# System_wired.net
KiCad netlist of a schematic drawn in Altium Designer
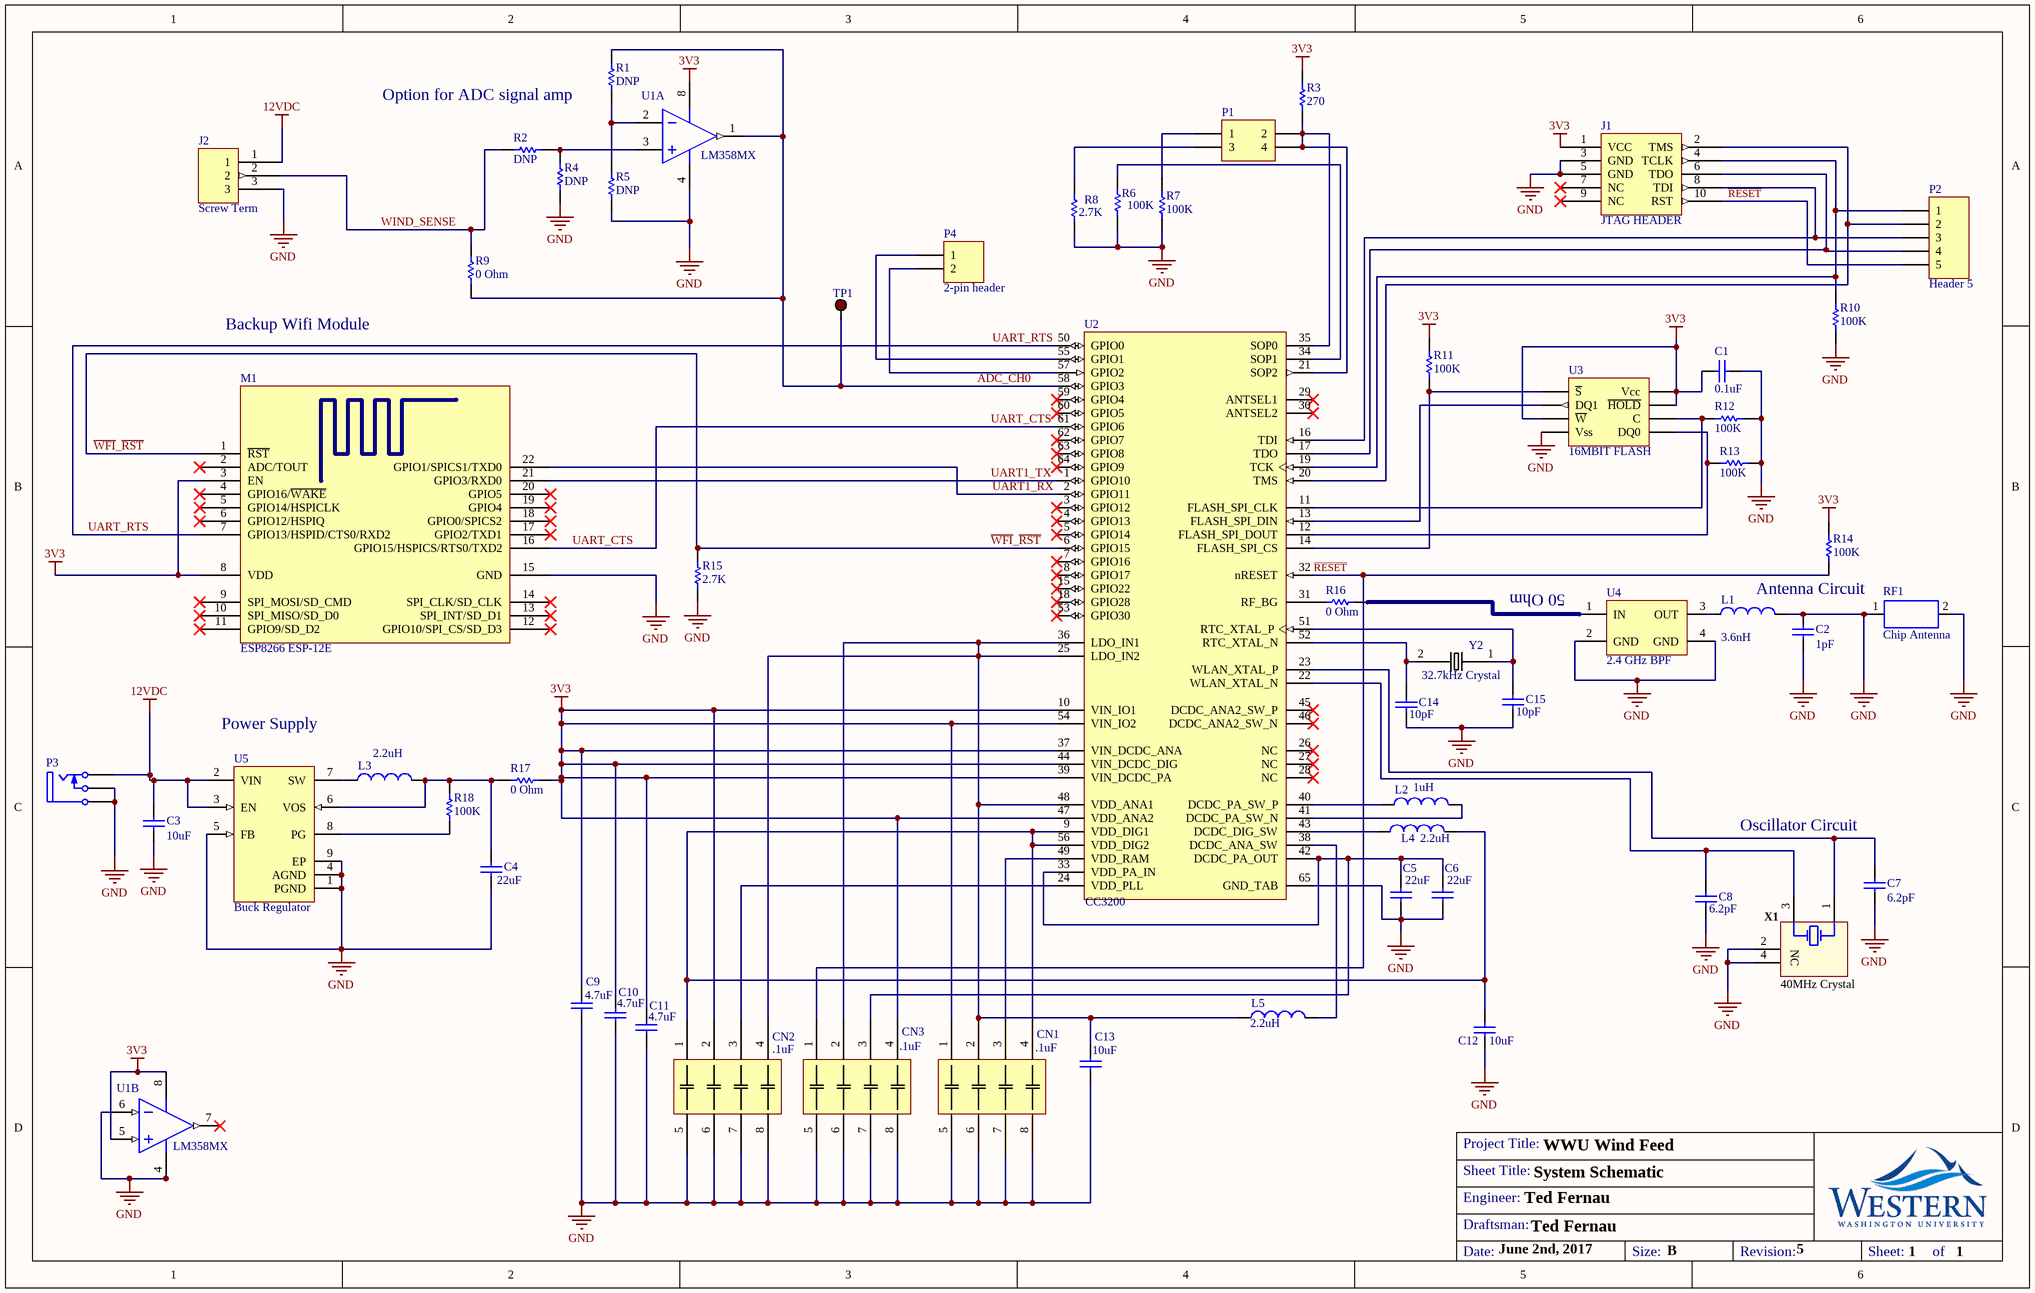
[diagram p0: System_wired.SchDoc]

(export (version "E")
  (design (tool "Eeschema 10.0.6"))
  (components
    (comp (ref "C1")
      (value "0.1uF")
      (footprint "CAPC0603(1608)100_M")
      (description "CAP 10uF 10V ±20% 0603 (1608 Metric) Thickness 1mm SMD")
      (fields (field (name "TOLERANCE") "Â±20%") (field (name "Comment") "CAP 10uF 10V 0603(1608)"))
      (libsource (lib "Altium Content Vault") (part "CMP-1035-02800-1"))
    )
    (comp (ref "C2")
      (value "1pF")
      (footprint "CAPC0603(1608)100_M")
      (description "CAP 10uF 10V ±20% 0603 (1608 Metric) Thickness 1mm SMD")
      (fields (field (name "TOLERANCE") "Â±20%") (field (name "Comment") "CAP 10uF 10V 0603(1608)"))
      (libsource (lib "Altium Content Vault") (part "CMP-1035-02800-1"))
    )
    (comp (ref "C3")
      (value "10uF")
      (footprint "CAPC0603(1608)100_M")
      (description "CAP 10uF 10V ±20% 0603 (1608 Metric) Thickness 1mm SMD")
      (fields (field (name "TOLERANCE") "Â±20%") (field (name "Comment") "CAP 10uF 10V 0603(1608)"))
      (libsource (lib "Altium Content Vault") (part "CMP-1035-02800-1"))
    )
    (comp (ref "C4")
      (value "22uF")
      (footprint "CAPC0603(1608)100_L")
      (description "0603 (1608 Metric) Chip Capacitor")
      (libsource (lib "Altium Content Vault") (part "CMP-1590-00005-1"))
    )
    (comp (ref "C5")
      (value "22uF")
      (footprint "CAPC0603(1608)100_M")
      (description "CAP 10uF 10V ±20% 0603 (1608 Metric) Thickness 1mm SMD")
      (fields (field (name "TOLERANCE") "Â±20%") (field (name "Comment") "CAP 10uF 10V 0603(1608)"))
      (libsource (lib "Altium Content Vault") (part "CMP-1035-02800-1"))
    )
    (comp (ref "C6")
      (value "22uF")
      (footprint "CAPC0603(1608)100_M")
      (description "CAP 10uF 10V ±20% 0603 (1608 Metric) Thickness 1mm SMD")
      (fields (field (name "TOLERANCE") "Â±20%") (field (name "Comment") "CAP 10uF 10V 0603(1608)"))
      (libsource (lib "Altium Content Vault") (part "CMP-1035-02800-1"))
    )
    (comp (ref "C7")
      (value "6.2pF")
      (footprint "CAPC0603(1608)100_M")
      (description "CAP 10uF 10V ±20% 0603 (1608 Metric) Thickness 1mm SMD")
      (fields (field (name "TOLERANCE") "Â±20%") (field (name "Comment") "CAP 10uF 10V 0603(1608)"))
      (libsource (lib "Altium Content Vault") (part "CMP-1035-02800-1"))
    )
    (comp (ref "C8")
      (value "6.2pF")
      (footprint "CAPC0603(1608)100_M")
      (description "CAP 10uF 10V ±20% 0603 (1608 Metric) Thickness 1mm SMD")
      (fields (field (name "TOLERANCE") "Â±20%") (field (name "Comment") "CAP 10uF 10V 0603(1608)"))
      (libsource (lib "Altium Content Vault") (part "CMP-1035-02800-1"))
    )
    (comp (ref "C9")
      (value "4.7uF")
      (footprint "CAPC0603(1608)100_M")
      (description "CAP 10uF 10V ±20% 0603 (1608 Metric) Thickness 1mm SMD")
      (fields (field (name "TOLERANCE") "Â±20%") (field (name "Comment") "CAP 10uF 10V 0603(1608)"))
      (libsource (lib "Altium Content Vault") (part "CMP-1035-02800-1"))
    )
    (comp (ref "C10")
      (value "4.7uF")
      (footprint "CAPC0603(1608)100_M")
      (description "CAP 10uF 10V ±20% 0603 (1608 Metric) Thickness 1mm SMD")
      (fields (field (name "TOLERANCE") "Â±20%") (field (name "Comment") "CAP 10uF 10V 0603(1608)"))
      (libsource (lib "Altium Content Vault") (part "CMP-1035-02800-1"))
    )
    (comp (ref "C11")
      (value "4.7uF")
      (footprint "CAPC0603(1608)100_M")
      (description "CAP 10uF 10V ±20% 0603 (1608 Metric) Thickness 1mm SMD")
      (fields (field (name "TOLERANCE") "Â±20%") (field (name "Comment") "CAP 10uF 10V 0603(1608)"))
      (libsource (lib "Altium Content Vault") (part "CMP-1035-02800-1"))
    )
    (comp (ref "C12")
      (value "10uF")
      (footprint "CAPC0603(1608)100_M")
      (description "CAP 10uF 10V ±20% 0603 (1608 Metric) Thickness 1mm SMD")
      (fields (field (name "TOLERANCE") "Â±20%") (field (name "Comment") "CAP 10uF 10V 0603(1608)"))
      (libsource (lib "Altium Content Vault") (part "CMP-1035-02800-1"))
    )
    (comp (ref "C13")
      (value "10uF")
      (footprint "CAPC0603(1608)100_M")
      (description "CAP 10uF 10V ±20% 0603 (1608 Metric) Thickness 1mm SMD")
      (fields (field (name "TOLERANCE") "Â±20%") (field (name "Comment") "CAP 10uF 10V 0603(1608)"))
      (libsource (lib "Altium Content Vault") (part "CMP-1035-02800-1"))
    )
    (comp (ref "C14")
      (value "10pF")
      (footprint "CAPC0603(1608)100_M")
      (description "CAP 10uF 10V ±20% 0603 (1608 Metric) Thickness 1mm SMD")
      (fields (field (name "TOLERANCE") "Â±20%") (field (name "Comment") "CAP 10uF 10V 0603(1608)"))
      (libsource (lib "Altium Content Vault") (part "CMP-1035-02800-1"))
    )
    (comp (ref "C15")
      (value "10pF")
      (footprint "CAPC0603(1608)100_M")
      (description "CAP 10uF 10V ±20% 0603 (1608 Metric) Thickness 1mm SMD")
      (fields (field (name "TOLERANCE") "Â±20%") (field (name "Comment") "CAP 10uF 10V 0603(1608)"))
      (libsource (lib "Altium Content Vault") (part "CMP-1035-02800-1"))
    )
    (comp (ref "CN1")
      (value ".1uF")
      (footprint "Cap. Array 0612")
      (libsource (lib "Schematic_Parts") (part "Cap. Array 0612"))
    )
    (comp (ref "CN2")
      (value ".1uF")
      (footprint "Cap. Array 0612")
      (libsource (lib "Schematic_Parts") (part "Cap. Array 0612"))
    )
    (comp (ref "CN3")
      (value ".1uF")
      (footprint "Cap. Array 0612")
      (libsource (lib "Schematic_Parts") (part "Cap. Array 0612"))
    )
    (comp (ref "J1")
      (value "JTAG HEADER")
      (footprint "FTSH-105-01-L-DV-K")
      (description "10 pin 0.05\" pitch header for JTAG")
      (libsource (lib "WWUEE_SchematicLibrary") (part "JTAG 10 PIN HEADER"))
    )
    (comp (ref "J2")
      (value "Screw Term")
      (footprint "SCREW TERM 3 PIN 3.5mm")
      (libsource (lib "WWUEE_SchematicLibrary") (part "SCREW TERM 3.5mm 3pos"))
    )
    (comp (ref "L1")
      (value "3.6nH")
      (footprint "1608[0603]")
      (description "Inductor")
      (fields (field (name "PUBLISHER") "Altium Limited"))
      (libsource (lib "Miscellaneous Devices") (part "Inductor"))
    )
    (comp (ref "L2")
      (value "MLZ2012N100LT")
      (footprint "TDK-IND0805-125_V")
      (description "Multilayer Inductor, 10 uH, ±20%, 300 mOhm, 50MHz, 0805(2012)")
      (fields
        (field (name "MANUFACTURER") "TDK Corporation")
        (field (name "MANUFACTURER PART NUMBER") "MLZ2012N100LTD25")
        (field (name "INDUCTANCE") "1uH")
      )
      (libsource (lib "Altium Content Vault") (part "CMP-0266-00001-1"))
    )
    (comp (ref "L3")
      (value "MLZ2012N100LT")
      (footprint "TDK-IND0805-125_V")
      (description "Multilayer Inductor, 10 uH, ±20%, 300 mOhm, 50MHz, 0805(2012)")
      (fields
        (field (name "MANUFACTURER") "TDK Corporation")
        (field (name "MANUFACTURER PART NUMBER") "MLZ2012N100LTD25")
        (field (name "INDUCTANCE") "2.2uH")
      )
      (libsource (lib "Altium Content Vault") (part "CMP-0266-00001-1"))
    )
    (comp (ref "L4")
      (value "MLZ2012N100LT")
      (footprint "TDK-IND0805-125_V")
      (description "Multilayer Inductor, 10 uH, ±20%, 300 mOhm, 50MHz, 0805(2012)")
      (fields
        (field (name "MANUFACTURER") "TDK Corporation")
        (field (name "MANUFACTURER PART NUMBER") "MLZ2012N100LTD25")
        (field (name "INDUCTANCE") "2.2uH")
      )
      (libsource (lib "Altium Content Vault") (part "CMP-0266-00001-1"))
    )
    (comp (ref "L5")
      (value "MLZ2012N100LT")
      (footprint "TDK-IND0805-125_V")
      (description "Multilayer Inductor, 10 uH, ±20%, 300 mOhm, 50MHz, 0805(2012)")
      (fields
        (field (name "MANUFACTURER") "TDK Corporation")
        (field (name "MANUFACTURER PART NUMBER") "MLZ2012N100LTD25")
        (field (name "INDUCTANCE") "2.2uH")
      )
      (libsource (lib "Altium Content Vault") (part "CMP-0266-00001-1"))
    )
    (comp (ref "M1")
      (value "ESP8266 ESP-12E")
      (footprint "ESP8266 ESP-12-E")
      (description "ESP8266 ESP-12-E")
      (libsource (lib "ESP8266") (part "ESP8266 ESP-12-E"))
    )
    (comp (ref "P1")
      (value "Header 2X2")
      (footprint "HDR2X2")
      (description "Header, 2-Pin, Dual row")
      (fields (field (name "PUBLISHER") "Altium Limited"))
      (libsource (lib "Miscellaneous Connectors") (part "Header 2X2"))
    )
    (comp (ref "P2")
      (value "Header 5")
      (footprint "HDR1X5")
      (description "Header, 5-Pin")
      (fields (field (name "PUBLISHER") "Altium Limited"))
      (libsource (lib "Miscellaneous Connectors") (part "Header 5"))
    )
    (comp (ref "P3")
      (value "RASM722X")
      (footprint "SWIT-RASM722X_V")
      (description "Power Jack, 5 A, 250 V, 3-Pin SMD, RoHS, Bulk")
      (libsource (lib "Altium Content Vault") (part "CMP-1772-00002-1"))
    )
    (comp (ref "P4")
      (value "2-pin header")
      (footprint "HDR1X2")
      (description "Header, 2-Pin")
      (fields (field (name "PUBLISHER") "Altium Limited"))
      (libsource (lib "Miscellaneous Connectors") (part "Header 2"))
    )
    (comp (ref "R1")
      (value "DNP")
      (footprint "RESC0603(1608)_N")
      (description "Jumper 0603 (1608 Metric)")
      (fields (field (name "POWER") "None"))
      (libsource (lib "Altium Content Vault") (part "CMP-1012-00001-1"))
    )
    (comp (ref "R2")
      (value "DNP")
      (footprint "RESC0603(1608)_N")
      (description "Jumper 0603 (1608 Metric)")
      (fields (field (name "POWER") "None"))
      (libsource (lib "Altium Content Vault") (part "CMP-1012-00001-1"))
    )
    (comp (ref "R3")
      (value "270")
      (footprint "RESC0805(2012)_L")
      (description "100K 0.125W 5% 0805 (2012 Metric)  SMD")
      (fields (field (name "TOLERANCE") "5 %") (field (name "POWER") "0.125 W"))
      (libsource (lib "Altium Content Vault") (part "CMP-1013-00122-1"))
    )
    (comp (ref "R4")
      (value "DNP")
      (footprint "RESC0603(1608)_N")
      (description "Jumper 0603 (1608 Metric)")
      (fields (field (name "POWER") "None"))
      (libsource (lib "Altium Content Vault") (part "CMP-1012-00001-1"))
    )
    (comp (ref "R5")
      (value "DNP")
      (footprint "RESC0603(1608)_N")
      (description "Jumper 0603 (1608 Metric)")
      (fields (field (name "POWER") "None"))
      (libsource (lib "Altium Content Vault") (part "CMP-1012-00001-1"))
    )
    (comp (ref "R6")
      (value "100K")
      (footprint "RESC0805(2012)_L")
      (description "100K 0.125W 5% 0805 (2012 Metric)  SMD")
      (fields (field (name "TOLERANCE") "5 %") (field (name "POWER") "0.125 W"))
      (libsource (lib "Altium Content Vault") (part "RES"))
    )
    (comp (ref "R7")
      (value "100K")
      (footprint "RESC0805(2012)_L")
      (description "100K 0.125W 5% 0805 (2012 Metric)  SMD")
      (fields (field (name "TOLERANCE") "5 %") (field (name "POWER") "0.125 W"))
      (libsource (lib "Altium Content Vault") (part "RES"))
    )
    (comp (ref "R8")
      (value "2.7K")
      (footprint "RESC0805(2012)_L")
      (description "100K 0.125W 5% 0805 (2012 Metric)  SMD")
      (fields (field (name "TOLERANCE") "5 %") (field (name "POWER") "0.125 W"))
      (libsource (lib "Altium Content Vault") (part "CMP-1013-00122-1"))
    )
    (comp (ref "R9")
      (value "0 Ohm")
      (footprint "RESC0603(1608)_N")
      (description "Jumper 0603 (1608 Metric)")
      (fields (field (name "POWER") "None"))
      (libsource (lib "Altium Content Vault") (part "RES"))
    )
    (comp (ref "R10")
      (value "100K")
      (footprint "RESC0805(2012)_L")
      (description "100K 0.125W 5% 0805 (2012 Metric)  SMD")
      (fields (field (name "TOLERANCE") "5 %") (field (name "POWER") "0.125 W"))
      (libsource (lib "Altium Content Vault") (part "RES"))
    )
    (comp (ref "R11")
      (value "100K")
      (footprint "RESC0805(2012)_L")
      (description "100K 0.125W 5% 0805 (2012 Metric)  SMD")
      (fields (field (name "TOLERANCE") "5 %") (field (name "POWER") "0.125 W"))
      (libsource (lib "Altium Content Vault") (part "RES"))
    )
    (comp (ref "R12")
      (value "100K")
      (footprint "RESC0805(2012)_L")
      (description "100K 0.125W 5% 0805 (2012 Metric)  SMD")
      (fields (field (name "TOLERANCE") "5 %") (field (name "POWER") "0.125 W"))
      (libsource (lib "Altium Content Vault") (part "RES"))
    )
    (comp (ref "R13")
      (value "100K")
      (footprint "RESC0805(2012)_L")
      (description "100K 0.125W 5% 0805 (2012 Metric)  SMD")
      (fields (field (name "TOLERANCE") "5 %") (field (name "POWER") "0.125 W"))
      (libsource (lib "Altium Content Vault") (part "RES"))
    )
    (comp (ref "R14")
      (value "100K")
      (footprint "RESC0805(2012)_L")
      (description "100K 0.125W 5% 0805 (2012 Metric)  SMD")
      (fields (field (name "TOLERANCE") "5 %") (field (name "POWER") "0.125 W"))
      (libsource (lib "Altium Content Vault") (part "RES"))
    )
    (comp (ref "R15")
      (value "2.7K")
      (footprint "RESC0805(2012)_L")
      (description "100K 0.125W 5% 0805 (2012 Metric)  SMD")
      (fields (field (name "TOLERANCE") "5 %") (field (name "POWER") "0.125 W"))
      (libsource (lib "Altium Content Vault") (part "RES"))
    )
    (comp (ref "R16")
      (value "0 Ohm")
      (footprint "RESC0603(1608)_N")
      (description "Jumper 0603 (1608 Metric)")
      (fields (field (name "POWER") "None"))
      (libsource (lib "Altium Content Vault") (part "RES"))
    )
    (comp (ref "R17")
      (value "0 Ohm")
      (footprint "RESC0603(1608)_N")
      (description "Jumper 0603 (1608 Metric)")
      (fields (field (name "POWER") "None"))
      (libsource (lib "Altium Content Vault") (part "CMP-1012-00001-1"))
    )
    (comp (ref "R18")
      (value "100K")
      (footprint "RESC0805(2012)_L")
      (description "100K 0.125W 5% 0805 (2012 Metric)  SMD")
      (fields (field (name "TOLERANCE") "5 %") (field (name "POWER") "0.125 W"))
      (libsource (lib "Altium Content Vault") (part "CMP-1013-00122-1"))
    )
    (comp (ref "RF1")
      (value "Chip Antenna")
      (footprint "TAYO-AH316M-2_N")
      (description "Chip Antenna, 2.4 to 2.5 GHz, -40 to 85 degC, 2-Pin SMD, Pb-Free, Tape and Reel")
      (fields (field (name "TOLERANCE") "10%"))
      (libsource (lib "Altium Content Vault") (part "CMP-1660-00004-1"))
    )
    (comp (ref "TP1")
      (value "5001")
      (footprint "Keystone_5001")
      (description "TEST POINT PC MINI .040\"D BLACK")
      (fields (field (name "MANUFACTURER") "Keystone Electronics"))
      (libsource (lib "WWUEE_SchematicLibrary") (part "TEST POINT"))
    )
    (comp (ref "U1")
      (value "LM358MX")
      (footprint "M08A_L")
      (description "Low Power Dual Operational Amplifier, 8-pin Narrow SOIC")
      (fields (field (name "MANUFACTURER") "National Semiconductor"))
      (libsource (lib "Altium Content Vault") (part "CMP-0055-00630-1"))
    )
    (comp (ref "U2")
      (value "CC3200")
      (footprint "TI-RGC64-7300x7300TP_L")
      (fields (field (name "PARTNUMBER") "CC3200R1M2RGC") (field (name "MANUFACTURER") "Texas Instruments"))
      (libsource (lib "altium-import") (part "root_0_CMP-1530-00002-1_"))
    )
    (comp (ref "U3")
      (value "16MBIT FLASH")
      (footprint "8SOIC")
      (description "16 MBIT FLASH SPI 8SOIC")
      (libsource (lib "WWUEE_SchematicLibrary") (part "FLASH SPI 16MBIT"))
    )
    (comp (ref "U4")
      (value "2.4 GHz BPF")
      (footprint "TDK-DEA202450BT-1294C1-H_V")
      (description "2.4 GHz Filter")
      (fields (field (name "TOLERANCE") "1%"))
      (libsource (lib "Altium Content Vault") (part "CMP-1663-00013-1"))
    )
    (comp (ref "U5")
      (value "Buck Regulator")
      (footprint "DSG0008A_V")
      (fields (field (name "MANUFACTURER") "Texas Instruments") (field (name "PARTNUMBER") "TPS62172DSGR"))
      (libsource (lib "Altium Content Vault") (part "CMP-0323-00337-3"))
    )
    (comp (ref "X1")
      (value "40MHz Crystal")
      (footprint "AVX-CX3225GB-4_V")
      (description "Crystal Unit, 8 pF, 25000 kHz, -10 to 70 degC, 4-Pin 3.2 x 2.5 x 0.8 mm SMD, RoHS, Tape and Reel")
      (fields (field (name "MANUFACTURER") "Kyocera") (field (name "PARTNUMBER") "CX3225GB25000D0HEQCC"))
      (libsource (lib "Altium Content Vault") (part "CMP-0614-00001-1"))
    )
    (comp (ref "Y2")
      (value "32.7kHz Crystal")
      (footprint "XTAL320X150X90")
      (description "ABS07 Series 32.768 kHz %C2%B120 ppm 12.5 pF -40 to %2B85 %C2%B0C SMT Low Profile Crystal")
      (fields (field (name "MF") "Abracon") (field (name "MP") "ABS07-32.768KHZ-T"))
      (libsource (lib "Schematic_Parts") (part "ABS07-32.768KHZ-T"))
    )
  )
  (nets
    (net (code "1") (name "/ADC_CH0") (class "Default")
      (node (ref "R1") (pin "2") (pinfunction "2_2") (pintype "passive"))
      (node (ref "R9") (pin "1") (pinfunction "1_1") (pintype "passive"))
      (node (ref "TP1") (pin "1") (pinfunction "TP_1") (pintype "passive"))
      (node (ref "U1") (pin "1") (pinfunction "OUTA_1") (pintype "output"))
      (node (ref "U2") (pin "58") (pinfunction "GPIO3_58") (pintype "bidirectional"))
    )
    (net (code "2") (name "/UART1_RX") (class "Default")
      (node (ref "M1") (pin "22") (pinfunction "GPIO1/SPICS1/TXD0_22") (pintype "passive"))
      (node (ref "U2") (pin "2") (pinfunction "GPIO11_2") (pintype "bidirectional"))
    )
    (net (code "3") (name "/UART1_TX") (class "Default")
      (node (ref "M1") (pin "21") (pinfunction "GPIO3/RXD0_21") (pintype "passive"))
      (node (ref "U2") (pin "1") (pinfunction "GPIO10_1") (pintype "bidirectional"))
    )
    (net (code "4") (name "/UART_CTS") (class "Default")
      (node (ref "M1") (pin "16") (pinfunction "GPIO15/HSPICS/RTS0/TXD2_16") (pintype "passive"))
      (node (ref "U2") (pin "61") (pinfunction "GPIO6_61") (pintype "bidirectional"))
    )
    (net (code "5") (name "/UART_RTS") (class "Default")
      (node (ref "M1") (pin "7") (pinfunction "GPIO13/HSPID/CTS0/RXD2_7") (pintype "passive"))
      (node (ref "U2") (pin "50") (pinfunction "GPIO0_50") (pintype "bidirectional"))
    )
    (net (code "6") (name "/WIND_SENSE") (class "Default")
      (node (ref "J2") (pin "2") (pinfunction "2_2") (pintype "output"))
      (node (ref "R2") (pin "2") (pinfunction "2_2") (pintype "passive"))
      (node (ref "R9") (pin "2") (pinfunction "2_2") (pintype "passive"))
    )
    (net (code "7") (name "/~{RESET}") (class "Default")
      (node (ref "CN3") (pin "1") (pinfunction "1_1") (pintype "passive"))
      (node (ref "J1") (pin "10") (pinfunction "RST_10") (pintype "output"))
      (node (ref "P2") (pin "5") (pinfunction "5_5") (pintype "passive"))
      (node (ref "R14") (pin "1") (pinfunction "1_1") (pintype "passive"))
      (node (ref "U2") (pin "32") (pinfunction "nRESET_32") (pintype "input"))
    )
    (net (code "8") (name "/~{WFI}_~{RST}") (class "Default")
      (node (ref "M1") (pin "1") (pinfunction "~{RST}_1") (pintype "passive"))
      (node (ref "R15") (pin "2") (pinfunction "2_2") (pintype "passive"))
      (node (ref "U2") (pin "6") (pinfunction "GPIO15_6") (pintype "bidirectional"))
    )
    (net (code "9") (name "3V3") (class "Default")
      (node (ref "C1") (pin "2") (pinfunction "2_2") (pintype "passive"))
      (node (ref "C10") (pin "2") (pinfunction "2_2") (pintype "passive"))
      (node (ref "C11") (pin "2") (pinfunction "2_2") (pintype "passive"))
      (node (ref "C9") (pin "2") (pinfunction "2_2") (pintype "passive"))
      (node (ref "CN1") (pin "1") (pinfunction "1_1") (pintype "passive"))
      (node (ref "CN2") (pin "2") (pinfunction "2_2") (pintype "passive"))
      (node (ref "CN3") (pin "4") (pinfunction "4_4") (pintype "passive"))
      (node (ref "J1") (pin "1") (pinfunction "VCC_1") (pintype "passive"))
      (node (ref "M1") (pin "3") (pinfunction "EN_3") (pintype "passive"))
      (node (ref "M1") (pin "8") (pinfunction "VDD_8") (pintype "passive"))
      (node (ref "R11") (pin "2") (pinfunction "2_2") (pintype "passive"))
      (node (ref "R14") (pin "2") (pinfunction "2_2") (pintype "passive"))
      (node (ref "R17") (pin "1") (pinfunction "1_1") (pintype "passive"))
      (node (ref "R3") (pin "2") (pinfunction "2_2") (pintype "passive"))
      (node (ref "U1") (pin "5") (pinfunction "INB+_5") (pintype "input"))
      (node (ref "U1") (pin "8") (pinfunction "V+_8") (pintype "power_in"))
      (node (ref "U2") (pin "10") (pinfunction "VIN_IO1_10") (pintype "power_in"))
      (node (ref "U2") (pin "37") (pinfunction "VIN_DCDC_ANA_37") (pintype "power_in"))
      (node (ref "U2") (pin "39") (pinfunction "VIN_DCDC_PA_39") (pintype "power_in"))
      (node (ref "U2") (pin "44") (pinfunction "VIN_DCDC_DIG_44") (pintype "power_in"))
      (node (ref "U2") (pin "47") (pinfunction "VDD_ANA2_47") (pintype "power_in"))
      (node (ref "U2") (pin "54") (pinfunction "VIN_IO2_54") (pintype "power_in"))
      (node (ref "U3") (pin "3") (pinfunction "~{W}_3") (pintype "passive"))
      (node (ref "U3") (pin "7") (pinfunction "~{HOLD}_7") (pintype "passive"))
      (node (ref "U3") (pin "8") (pinfunction "Vcc_8") (pintype "passive"))
    )
    (net (code "10") (name "12VDC") (class "Default")
      (node (ref "C3") (pin "2") (pinfunction "2_2") (pintype "passive"))
      (node (ref "J2") (pin "1") (pinfunction "1_1") (pintype "passive"))
      (node (ref "P3") (pin "2") (pinfunction "TIP_2") (pintype "passive"))
      (node (ref "U5") (pin "2") (pinfunction "VIN_2") (pintype "power_in"))
      (node (ref "U5") (pin "3") (pinfunction "EN_3") (pintype "input"))
    )
    (net (code "11") (name "GND") (class "Default")
      (node (ref "C1") (pin "1") (pinfunction "1_1") (pintype "passive"))
      (node (ref "C10") (pin "1") (pinfunction "1_1") (pintype "passive"))
      (node (ref "C11") (pin "1") (pinfunction "1_1") (pintype "passive"))
      (node (ref "C12") (pin "2") (pinfunction "2_2") (pintype "passive"))
      (node (ref "C13") (pin "2") (pinfunction "2_2") (pintype "passive"))
      (node (ref "C14") (pin "1") (pinfunction "1_1") (pintype "passive"))
      (node (ref "C15") (pin "1") (pinfunction "1_1") (pintype "passive"))
      (node (ref "C2") (pin "1") (pinfunction "1_1") (pintype "passive"))
      (node (ref "C2") (pin "2") (pinfunction "2_2") (pintype "passive"))
      (node (ref "C3") (pin "1") (pinfunction "1_1") (pintype "passive"))
      (node (ref "C4") (pin "1") (pinfunction "1_1") (pintype "passive"))
      (node (ref "C5") (pin "2") (pinfunction "2_2") (pintype "passive"))
      (node (ref "C6") (pin "2") (pinfunction "2_2") (pintype "passive"))
      (node (ref "C7") (pin "1") (pinfunction "1_1") (pintype "passive"))
      (node (ref "C8") (pin "1") (pinfunction "1_1") (pintype "passive"))
      (node (ref "C9") (pin "1") (pinfunction "1_1") (pintype "passive"))
      (node (ref "CN1") (pin "5") (pinfunction "5_5") (pintype "passive"))
      (node (ref "CN1") (pin "6") (pinfunction "6_6") (pintype "passive"))
      (node (ref "CN1") (pin "7") (pinfunction "7_7") (pintype "passive"))
      (node (ref "CN1") (pin "8") (pinfunction "8_8") (pintype "passive"))
      (node (ref "CN2") (pin "5") (pinfunction "5_5") (pintype "passive"))
      (node (ref "CN2") (pin "6") (pinfunction "6_6") (pintype "passive"))
      (node (ref "CN2") (pin "7") (pinfunction "7_7") (pintype "passive"))
      (node (ref "CN2") (pin "8") (pinfunction "8_8") (pintype "passive"))
      (node (ref "CN3") (pin "5") (pinfunction "5_5") (pintype "passive"))
      (node (ref "CN3") (pin "6") (pinfunction "6_6") (pintype "passive"))
      (node (ref "CN3") (pin "7") (pinfunction "7_7") (pintype "passive"))
      (node (ref "CN3") (pin "8") (pinfunction "8_8") (pintype "passive"))
      (node (ref "J1") (pin "3") (pinfunction "GND_3") (pintype "passive"))
      (node (ref "J1") (pin "5") (pinfunction "GND_5") (pintype "passive"))
      (node (ref "J2") (pin "3") (pinfunction "3_3") (pintype "passive"))
      (node (ref "L1") (pin "2") (pinfunction "2_2") (pintype "passive"))
      (node (ref "M1") (pin "15") (pinfunction "GND_15") (pintype "passive"))
      (node (ref "P3") (pin "1") (pinfunction "SLEEVE_1") (pintype "passive"))
      (node (ref "P3") (pin "3") (pinfunction "SHUNT_3") (pintype "passive"))
      (node (ref "R10") (pin "1") (pinfunction "1_1") (pintype "passive"))
      (node (ref "R12") (pin "1") (pinfunction "1_1") (pintype "passive"))
      (node (ref "R13") (pin "1") (pinfunction "1_1") (pintype "passive"))
      (node (ref "R15") (pin "1") (pinfunction "1_1") (pintype "passive"))
      (node (ref "R4") (pin "1") (pinfunction "1_1") (pintype "passive"))
      (node (ref "R5") (pin "1") (pinfunction "1_1") (pintype "passive"))
      (node (ref "R6") (pin "1") (pinfunction "1_1") (pintype "passive"))
      (node (ref "R7") (pin "1") (pinfunction "1_1") (pintype "passive"))
      (node (ref "R8") (pin "1") (pinfunction "1_1") (pintype "passive"))
      (node (ref "RF1") (pin "1") (pinfunction "1_1") (pintype "passive"))
      (node (ref "RF1") (pin "2") (pinfunction "2_2") (pintype "passive"))
      (node (ref "U1") (pin "4") (pinfunction "GND_4") (pintype "power_in"))
      (node (ref "U1") (pin "6") (pinfunction "INB-_6") (pintype "input"))
      (node (ref "U2") (pin "65") (pinfunction "GND_TAB_65") (pintype "power_in"))
      (node (ref "U3") (pin "4") (pinfunction "Vss_4") (pintype "passive"))
      (node (ref "U4") (pin "2") (pinfunction "GND_2") (pintype "power_in"))
      (node (ref "U4") (pin "4") (pinfunction "GND_4") (pintype "power_in"))
      (node (ref "U5") (pin "1") (pinfunction "PGND_1") (pintype "power_in"))
      (node (ref "U5") (pin "4") (pinfunction "AGND_4") (pintype "power_in"))
      (node (ref "U5") (pin "5") (pinfunction "FB_5") (pintype "input"))
      (node (ref "U5") (pin "9") (pinfunction "EP_9") (pintype "power_in"))
      (node (ref "X1") (pin "2") (pinfunction "GND_2") (pintype "passive"))
      (node (ref "X1") (pin "4") (pinfunction "GND_4") (pintype "passive"))
    )
    (net (code "12") (name "Net-(J1-TCLK)") (class "Default")
      (node (ref "J1") (pin "4") (pinfunction "TCLK_4") (pintype "output"))
      (node (ref "P2") (pin "1") (pinfunction "1_1") (pintype "passive"))
      (node (ref "R10") (pin "2") (pinfunction "2_2") (pintype "passive"))
      (node (ref "U2") (pin "19") (pinfunction "TCK_19") (pintype "input"))
    )
    (net (code "13") (name "Net-(J1-TDI)") (class "Default")
      (node (ref "J1") (pin "8") (pinfunction "TDI_8") (pintype "output"))
      (node (ref "P2") (pin "3") (pinfunction "3_3") (pintype "passive"))
      (node (ref "U2") (pin "16") (pinfunction "TDI_16") (pintype "input"))
    )
    (net (code "14") (name "Net-(J1-TDO)") (class "Default")
      (node (ref "J1") (pin "6") (pinfunction "TDO_6") (pintype "passive"))
      (node (ref "P2") (pin "4") (pinfunction "4_4") (pintype "passive"))
      (node (ref "U2") (pin "17") (pinfunction "TDO_17") (pintype "tri_state"))
    )
    (net (code "15") (name "Net-(J1-TMS)") (class "Default")
      (node (ref "J1") (pin "2") (pinfunction "TMS_2") (pintype "output"))
      (node (ref "P2") (pin "2") (pinfunction "2_2") (pintype "passive"))
      (node (ref "U2") (pin "20") (pinfunction "TMS_20") (pintype "input"))
    )
    (net (code "16") (name "Net-(P1-Pad1)") (class "Default")
      (node (ref "P1") (pin "1") (pinfunction "1_1") (pintype "passive"))
      (node (ref "R7") (pin "2") (pinfunction "2_2") (pintype "passive"))
    )
    (net (code "17") (name "Net-(P1-Pad3)") (class "Default")
      (node (ref "P1") (pin "3") (pinfunction "3_3") (pintype "passive"))
      (node (ref "R8") (pin "2") (pinfunction "2_2") (pintype "passive"))
    )
    (net (code "18") (name "Net-(U1A-INA+)") (class "Default")
      (node (ref "R2") (pin "1") (pinfunction "1_1") (pintype "passive"))
      (node (ref "R4") (pin "2") (pinfunction "2_2") (pintype "passive"))
      (node (ref "U1") (pin "3") (pinfunction "INA+_3") (pintype "input"))
    )
    (net (code "19") (name "Net-(U1A-INA-)") (class "Default")
      (node (ref "R1") (pin "1") (pinfunction "1_1") (pintype "passive"))
      (node (ref "R5") (pin "2") (pinfunction "2_2") (pintype "passive"))
      (node (ref "U1") (pin "2") (pinfunction "INA-_2") (pintype "input"))
    )
    (net (code "20") (name "Net-(U2-DCDC_ANA_SW)") (class "Default")
      (node (ref "L5") (pin "2") (pinfunction "2_2") (pintype "passive"))
      (node (ref "U2") (pin "38") (pinfunction "DCDC_ANA_SW_38") (pintype "power_in"))
    )
    (net (code "21") (name "Net-(U2-DCDC_DIG_SW)") (class "Default")
      (node (ref "L4") (pin "1") (pinfunction "1_1") (pintype "passive"))
      (node (ref "U2") (pin "43") (pinfunction "DCDC_DIG_SW_43") (pintype "power_in"))
    )
    (net (code "22") (name "Net-(U2-DCDC_PA_OUT)") (class "Default")
      (node (ref "C5") (pin "1") (pinfunction "1_1") (pintype "passive"))
      (node (ref "C6") (pin "1") (pinfunction "1_1") (pintype "passive"))
      (node (ref "CN3") (pin "3") (pinfunction "3_3") (pintype "passive"))
      (node (ref "U2") (pin "33") (pinfunction "VDD_PA_IN_33") (pintype "power_in"))
      (node (ref "U2") (pin "42") (pinfunction "DCDC_PA_OUT_42") (pintype "power_in"))
    )
    (net (code "23") (name "Net-(U2-DCDC_PA_SW_N)") (class "Default")
      (node (ref "L2") (pin "2") (pinfunction "2_2") (pintype "passive"))
      (node (ref "U2") (pin "41") (pinfunction "DCDC_PA_SW_N_41") (pintype "power_in"))
    )
    (net (code "24") (name "Net-(U2-DCDC_PA_SW_P)") (class "Default")
      (node (ref "L2") (pin "1") (pinfunction "1_1") (pintype "passive"))
      (node (ref "U2") (pin "40") (pinfunction "DCDC_PA_SW_P_40") (pintype "power_in"))
    )
    (net (code "25") (name "Net-(U2-FLASH_SPI_CLK)") (class "Default")
      (node (ref "R12") (pin "2") (pinfunction "2_2") (pintype "passive"))
      (node (ref "U2") (pin "11") (pinfunction "FLASH_SPI_CLK_11") (pintype "tri_state"))
      (node (ref "U3") (pin "6") (pinfunction "C_6") (pintype "passive"))
    )
    (net (code "26") (name "Net-(U2-FLASH_SPI_CS)") (class "Default")
      (node (ref "R11") (pin "1") (pinfunction "1_1") (pintype "passive"))
      (node (ref "U2") (pin "14") (pinfunction "FLASH_SPI_CS_14") (pintype "tri_state"))
      (node (ref "U3") (pin "1") (pinfunction "~{S}_1") (pintype "passive"))
    )
    (net (code "27") (name "Net-(U2-FLASH_SPI_DIN)") (class "Default")
      (node (ref "U2") (pin "13") (pinfunction "FLASH_SPI_DIN_13") (pintype "input"))
      (node (ref "U3") (pin "2") (pinfunction "DQ1_2") (pintype "output"))
    )
    (net (code "28") (name "Net-(U2-FLASH_SPI_DOUT)") (class "Default")
      (node (ref "R13") (pin "2") (pinfunction "2_2") (pintype "passive"))
      (node (ref "U2") (pin "12") (pinfunction "FLASH_SPI_DOUT_12") (pintype "tri_state"))
      (node (ref "U3") (pin "5") (pinfunction "DQ0_5") (pintype "passive"))
    )
    (net (code "29") (name "Net-(U2-GPIO1)") (class "Default")
      (node (ref "P4") (pin "1") (pinfunction "1_1") (pintype "passive"))
      (node (ref "U2") (pin "55") (pinfunction "GPIO1_55") (pintype "bidirectional"))
    )
    (net (code "30") (name "Net-(U2-GPIO2)") (class "Default")
      (node (ref "P4") (pin "2") (pinfunction "2_2") (pintype "passive"))
      (node (ref "U2") (pin "57") (pinfunction "GPIO2_57") (pintype "input"))
    )
    (net (code "31") (name "Net-(U2-LDO_IN1)") (class "Default")
      (node (ref "C13") (pin "1") (pinfunction "1_1") (pintype "passive"))
      (node (ref "CN1") (pin "2") (pinfunction "2_2") (pintype "passive"))
      (node (ref "CN2") (pin "4") (pinfunction "4_4") (pintype "passive"))
      (node (ref "CN3") (pin "2") (pinfunction "2_2") (pintype "passive"))
      (node (ref "L5") (pin "1") (pinfunction "1_1") (pintype "passive"))
      (node (ref "U2") (pin "25") (pinfunction "LDO_IN2_25") (pintype "power_in"))
      (node (ref "U2") (pin "36") (pinfunction "LDO_IN1_36") (pintype "power_in"))
      (node (ref "U2") (pin "48") (pinfunction "VDD_ANA1_48") (pintype "power_in"))
    )
    (net (code "32") (name "Net-(U2-RF_BG)") (class "Default")
      (node (ref "R16") (pin "2") (pinfunction "2_2") (pintype "passive"))
      (node (ref "U2") (pin "31") (pinfunction "RF_BG_31") (pintype "passive"))
    )
    (net (code "33") (name "Net-(U2-RTC_XTAL_N)") (class "Default")
      (node (ref "C14") (pin "2") (pinfunction "2_2") (pintype "passive"))
      (node (ref "U2") (pin "52") (pinfunction "RTC_XTAL_N_52") (pintype "passive"))
      (node (ref "Y2") (pin "2") (pinfunction "2_2") (pintype "passive"))
    )
    (net (code "34") (name "Net-(U2-RTC_XTAL_P)") (class "Default")
      (node (ref "C15") (pin "2") (pinfunction "2_2") (pintype "passive"))
      (node (ref "U2") (pin "51") (pinfunction "RTC_XTAL_P_51") (pintype "input"))
      (node (ref "Y2") (pin "1") (pinfunction "1_1") (pintype "passive"))
    )
    (net (code "35") (name "Net-(U2-SOP0)") (class "Default")
      (node (ref "P1") (pin "2") (pinfunction "2_2") (pintype "passive"))
      (node (ref "P1") (pin "4") (pinfunction "4_4") (pintype "passive"))
      (node (ref "R3") (pin "1") (pinfunction "1_1") (pintype "passive"))
      (node (ref "U2") (pin "21") (pinfunction "SOP2_21") (pintype "output"))
      (node (ref "U2") (pin "35") (pinfunction "SOP0_35") (pintype "passive"))
    )
    (net (code "36") (name "Net-(U2-SOP1)") (class "Default")
      (node (ref "R6") (pin "2") (pinfunction "2_2") (pintype "passive"))
      (node (ref "U2") (pin "34") (pinfunction "SOP1_34") (pintype "passive"))
    )
    (net (code "37") (name "Net-(U2-VDD_DIG1)") (class "Default")
      (node (ref "C12") (pin "1") (pinfunction "1_1") (pintype "passive"))
      (node (ref "CN1") (pin "4") (pinfunction "4_4") (pintype "passive"))
      (node (ref "CN2") (pin "1") (pinfunction "1_1") (pintype "passive"))
      (node (ref "L4") (pin "2") (pinfunction "2_2") (pintype "passive"))
      (node (ref "U2") (pin "56") (pinfunction "VDD_DIG2_56") (pintype "power_in"))
      (node (ref "U2") (pin "9") (pinfunction "VDD_DIG1_9") (pintype "power_in"))
    )
    (net (code "38") (name "Net-(U2-VDD_PLL)") (class "Default")
      (node (ref "CN2") (pin "3") (pinfunction "3_3") (pintype "passive"))
      (node (ref "U2") (pin "24") (pinfunction "VDD_PLL_24") (pintype "power_in"))
    )
    (net (code "39") (name "Net-(U2-VDD_RAM)") (class "Default")
      (node (ref "CN1") (pin "3") (pinfunction "3_3") (pintype "passive"))
      (node (ref "U2") (pin "49") (pinfunction "VDD_RAM_49") (pintype "power_in"))
    )
    (net (code "40") (name "Net-(U2-WLAN_XTAL_N)") (class "Default")
      (node (ref "C8") (pin "2") (pinfunction "2_2") (pintype "passive"))
      (node (ref "U2") (pin "22") (pinfunction "WLAN_XTAL_N_22") (pintype "passive"))
      (node (ref "X1") (pin "3") (pinfunction "HOT_3") (pintype "passive"))
    )
    (net (code "41") (name "Net-(U2-WLAN_XTAL_P)") (class "Default")
      (node (ref "C7") (pin "2") (pinfunction "2_2") (pintype "passive"))
      (node (ref "U2") (pin "23") (pinfunction "WLAN_XTAL_P_23") (pintype "passive"))
      (node (ref "X1") (pin "1") (pinfunction "HOT_1") (pintype "passive"))
    )
    (net (code "42") (name "Net-(U4-IN)") (class "Default")
      (node (ref "R16") (pin "1") (pinfunction "1_1") (pintype "passive"))
      (node (ref "U4") (pin "1") (pinfunction "IN_1") (pintype "power_in"))
    )
    (net (code "43") (name "Net-(U4-OUT)") (class "Default")
      (node (ref "L1") (pin "1") (pinfunction "1_1") (pintype "passive"))
      (node (ref "U4") (pin "3") (pinfunction "OUT_3") (pintype "power_in"))
    )
    (net (code "44") (name "Net-(U5-PG)") (class "Default")
      (node (ref "R18") (pin "1") (pinfunction "1_1") (pintype "passive"))
      (node (ref "U5") (pin "8") (pinfunction "PG_8") (pintype "tri_state"))
    )
    (net (code "45") (name "Net-(U5-SW)") (class "Default")
      (node (ref "L3") (pin "1") (pinfunction "1_1") (pintype "passive"))
      (node (ref "U5") (pin "7") (pinfunction "SW_7") (pintype "power_in"))
    )
    (net (code "46") (name "Net-(U5-VOS)") (class "Default")
      (node (ref "C4") (pin "2") (pinfunction "2_2") (pintype "passive"))
      (node (ref "L3") (pin "2") (pinfunction "2_2") (pintype "passive"))
      (node (ref "R17") (pin "2") (pinfunction "2_2") (pintype "passive"))
      (node (ref "R18") (pin "2") (pinfunction "2_2") (pintype "passive"))
      (node (ref "U5") (pin "6") (pinfunction "VOS_6") (pintype "input"))
    )
    (net (code "47") (name "unconnected-(J1-NC-Pad7)") (class "Default")
      (node (ref "J1") (pin "7") (pinfunction "NC_7") (pintype "passive+no_connect"))
    )
    (net (code "48") (name "unconnected-(J1-NC-Pad9)") (class "Default")
      (node (ref "J1") (pin "9") (pinfunction "NC_9") (pintype "passive+no_connect"))
    )
    (net (code "49") (name "unconnected-(M1-ADC{slash}TOUT-Pad2)") (class "Default")
      (node (ref "M1") (pin "2") (pinfunction "ADC/TOUT_2") (pintype "passive+no_connect"))
    )
    (net (code "50") (name "unconnected-(M1-GPIO0{slash}SPICS2-Pad18)") (class "Default")
      (node (ref "M1") (pin "18") (pinfunction "GPIO0/SPICS2_18") (pintype "passive+no_connect"))
    )
    (net (code "51") (name "unconnected-(M1-GPIO2{slash}TXD1-Pad17)") (class "Default")
      (node (ref "M1") (pin "17") (pinfunction "GPIO2/TXD1_17") (pintype "passive+no_connect"))
    )
    (net (code "52") (name "unconnected-(M1-GPIO4-Pad19)") (class "Default")
      (node (ref "M1") (pin "19") (pinfunction "GPIO4_19") (pintype "passive+no_connect"))
    )
    (net (code "53") (name "unconnected-(M1-GPIO5-Pad20)") (class "Default")
      (node (ref "M1") (pin "20") (pinfunction "GPIO5_20") (pintype "passive+no_connect"))
    )
    (net (code "54") (name "unconnected-(M1-GPIO9{slash}SD_D2-Pad11)") (class "Default")
      (node (ref "M1") (pin "11") (pinfunction "GPIO9/SD_D2_11") (pintype "passive+no_connect"))
    )
    (net (code "55") (name "unconnected-(M1-GPIO10{slash}SPI_CS{slash}SD_D3-Pad12)") (class "Default")
      (node (ref "M1") (pin "12") (pinfunction "GPIO10/SPI_CS/SD_D3_12") (pintype "passive+no_connect"))
    )
    (net (code "56") (name "unconnected-(M1-GPIO12{slash}HSPIQ-Pad6)") (class "Default")
      (node (ref "M1") (pin "6") (pinfunction "GPIO12/HSPIQ_6") (pintype "passive+no_connect"))
    )
    (net (code "57") (name "unconnected-(M1-GPIO14{slash}HSPICLK-Pad5)") (class "Default")
      (node (ref "M1") (pin "5") (pinfunction "GPIO14/HSPICLK_5") (pintype "passive+no_connect"))
    )
    (net (code "58") (name "unconnected-(M1-GPIO16{slash}~{WAKE}-Pad4)") (class "Default")
      (node (ref "M1") (pin "4") (pinfunction "GPIO16/~{WAKE}_4") (pintype "passive+no_connect"))
    )
    (net (code "59") (name "unconnected-(M1-SPI_CLK{slash}SD_CLK-Pad14)") (class "Default")
      (node (ref "M1") (pin "14") (pinfunction "SPI_CLK/SD_CLK_14") (pintype "passive+no_connect"))
    )
    (net (code "60") (name "unconnected-(M1-SPI_INT{slash}SD_D1-Pad13)") (class "Default")
      (node (ref "M1") (pin "13") (pinfunction "SPI_INT/SD_D1_13") (pintype "passive+no_connect"))
    )
    (net (code "61") (name "unconnected-(M1-SPI_MISO{slash}SD_D0-Pad10)") (class "Default")
      (node (ref "M1") (pin "10") (pinfunction "SPI_MISO/SD_D0_10") (pintype "passive+no_connect"))
    )
    (net (code "62") (name "unconnected-(M1-SPI_MOSI{slash}SD_CMD-Pad9)") (class "Default")
      (node (ref "M1") (pin "9") (pinfunction "SPI_MOSI/SD_CMD_9") (pintype "passive+no_connect"))
    )
    (net (code "63") (name "unconnected-(U1B-OUTB-Pad7)") (class "Default")
      (node (ref "U1") (pin "7") (pinfunction "OUTB_7") (pintype "output+no_connect"))
    )
    (net (code "64") (name "unconnected-(U2-ANTSEL1-Pad29)") (class "Default")
      (node (ref "U2") (pin "29") (pinfunction "ANTSEL1_29") (pintype "tri_state+no_connect"))
    )
    (net (code "65") (name "unconnected-(U2-ANTSEL2-Pad30)") (class "Default")
      (node (ref "U2") (pin "30") (pinfunction "ANTSEL2_30") (pintype "tri_state+no_connect"))
    )
    (net (code "66") (name "unconnected-(U2-DCDC_ANA2_SW_N-Pad46)") (class "Default")
      (node (ref "U2") (pin "46") (pinfunction "DCDC_ANA2_SW_N_46") (pintype "passive+no_connect"))
    )
    (net (code "67") (name "unconnected-(U2-DCDC_ANA2_SW_P-Pad45)") (class "Default")
      (node (ref "U2") (pin "45") (pinfunction "DCDC_ANA2_SW_P_45") (pintype "passive+no_connect"))
    )
    (net (code "68") (name "unconnected-(U2-GPIO4-Pad59)") (class "Default")
      (node (ref "U2") (pin "59") (pinfunction "GPIO4_59") (pintype "bidirectional+no_connect"))
    )
    (net (code "69") (name "unconnected-(U2-GPIO5-Pad60)") (class "Default")
      (node (ref "U2") (pin "60") (pinfunction "GPIO5_60") (pintype "bidirectional+no_connect"))
    )
    (net (code "70") (name "unconnected-(U2-GPIO7-Pad62)") (class "Default")
      (node (ref "U2") (pin "62") (pinfunction "GPIO7_62") (pintype "bidirectional+no_connect"))
    )
    (net (code "71") (name "unconnected-(U2-GPIO8-Pad63)") (class "Default")
      (node (ref "U2") (pin "63") (pinfunction "GPIO8_63") (pintype "bidirectional+no_connect"))
    )
    (net (code "72") (name "unconnected-(U2-GPIO9-Pad64)") (class "Default")
      (node (ref "U2") (pin "64") (pinfunction "GPIO9_64") (pintype "bidirectional+no_connect"))
    )
    (net (code "73") (name "unconnected-(U2-GPIO12-Pad3)") (class "Default")
      (node (ref "U2") (pin "3") (pinfunction "GPIO12_3") (pintype "bidirectional+no_connect"))
    )
    (net (code "74") (name "unconnected-(U2-GPIO13-Pad4)") (class "Default")
      (node (ref "U2") (pin "4") (pinfunction "GPIO13_4") (pintype "bidirectional+no_connect"))
    )
    (net (code "75") (name "unconnected-(U2-GPIO14-Pad5)") (class "Default")
      (node (ref "U2") (pin "5") (pinfunction "GPIO14_5") (pintype "bidirectional+no_connect"))
    )
    (net (code "76") (name "unconnected-(U2-GPIO16-Pad7)") (class "Default")
      (node (ref "U2") (pin "7") (pinfunction "GPIO16_7") (pintype "bidirectional+no_connect"))
    )
    (net (code "77") (name "unconnected-(U2-GPIO17-Pad8)") (class "Default")
      (node (ref "U2") (pin "8") (pinfunction "GPIO17_8") (pintype "bidirectional+no_connect"))
    )
    (net (code "78") (name "unconnected-(U2-GPIO22-Pad15)") (class "Default")
      (node (ref "U2") (pin "15") (pinfunction "GPIO22_15") (pintype "bidirectional+no_connect"))
    )
    (net (code "79") (name "unconnected-(U2-GPIO28-Pad18)") (class "Default")
      (node (ref "U2") (pin "18") (pinfunction "GPIO28_18") (pintype "bidirectional+no_connect"))
    )
    (net (code "80") (name "unconnected-(U2-GPIO30-Pad53)") (class "Default")
      (node (ref "U2") (pin "53") (pinfunction "GPIO30_53") (pintype "bidirectional+no_connect"))
    )
    (net (code "81") (name "unconnected-(U2-NC-Pad26)") (class "Default")
      (node (ref "U2") (pin "26") (pinfunction "NC_26") (pintype "passive+no_connect"))
    )
    (net (code "82") (name "unconnected-(U2-NC-Pad27)") (class "Default")
      (node (ref "U2") (pin "27") (pinfunction "NC_27") (pintype "passive+no_connect"))
    )
    (net (code "83") (name "unconnected-(U2-NC-Pad28)") (class "Default")
      (node (ref "U2") (pin "28") (pinfunction "NC_28") (pintype "passive+no_connect"))
    )
  )
)
